# Power_supply.net
KiCad netlist of a schematic drawn in Altium Designer
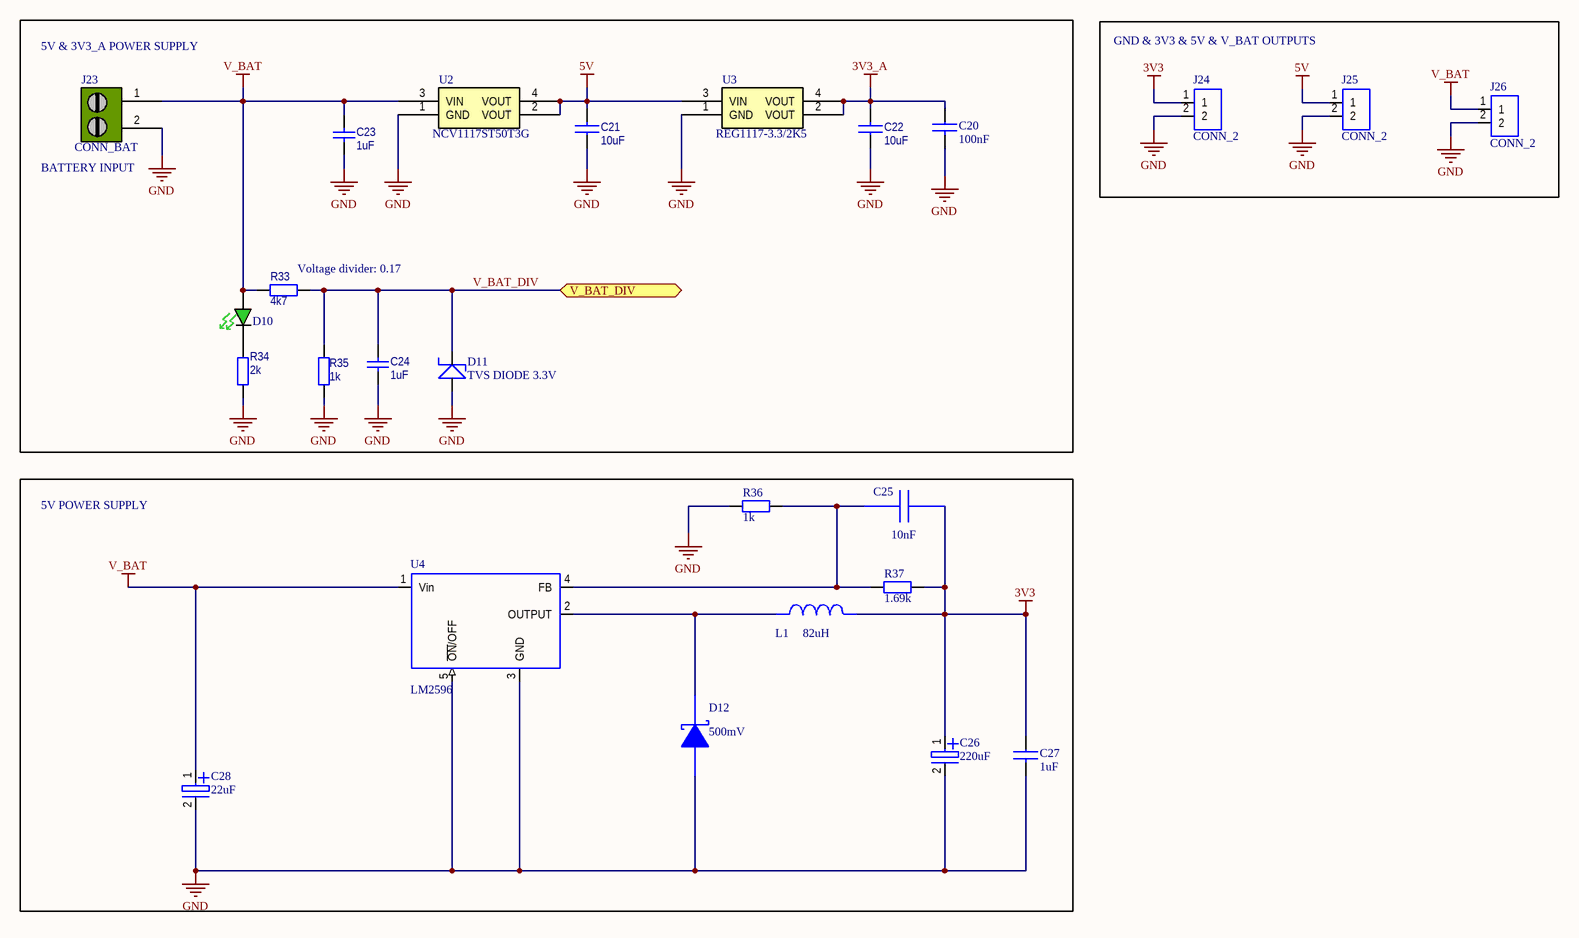
[diagram p0: Power_supply.SchDoc]

(export (version "E")
  (design (tool "Eeschema 10.0.6"))
  (components
    (comp (ref "C20")
      (value "100nF")
      (footprint "080503")
      (description "CAP CER 0.1UF 25V 10% X7R 0805")
      (libsource (lib "EISI") (part "CAPA"))
    )
    (comp (ref "C21")
      (value "10uF")
      (footprint "080501")
      (description "CAP CER 10UF 16V 20% X6S 0805")
      (libsource (lib "EISI") (part "CAPA"))
    )
    (comp (ref "C22")
      (value "10uF")
      (footprint "080501")
      (description "CAP CER 10UF 16V 20% X6S 0805")
      (libsource (lib "EISI") (part "CAPA"))
    )
    (comp (ref "C23")
      (value "1uF")
      (footprint "080503")
      (description "CAP CER 1UF 25V 10% X7R 0805")
      (libsource (lib "Miscellaneous Devices") (part "Cap Semi"))
    )
    (comp (ref "C24")
      (value "1uF")
      (footprint "080503")
      (description "CAP CER 1UF 25V 10% X7R 0805")
      (libsource (lib "Miscellaneous Devices") (part "Cap Semi"))
    )
    (comp (ref "C25")
      (value "10nF")
      (footprint "080503")
      (description "CAP CER 10nF 50V 10% X7R 0805")
      (libsource (lib "TI WEBENCH") (part "Cf"))
    )
    (comp (ref "C26")
      (value "220uF")
      (footprint "1411")
      (description "CAP TANT 220UF 4V 20% 1411")
      (libsource (lib "EISI") (part "CAPA_EL"))
    )
    (comp (ref "C27")
      (value "1uF")
      (footprint "080503")
      (description "CAP CER 1UF 25V 10% X7R 0805")
      (libsource (lib "EISI") (part "CAPA"))
    )
    (comp (ref "C28")
      (value "22uF")
      (footprint "2413")
      (description "CAP TANT 22UF 25V 10% 2413")
      (libsource (lib "EISI") (part "CAPA_EL"))
    )
    (comp (ref "D10")
      (value "LED")
      (footprint "LED_0805 - GREEN")
      (description "LED 2X1.2MM 570NM GN WTR CLR SMD")
      (libsource (lib "eDiode") (part "APT2012CGCK"))
    )
    (comp (ref "D11")
      (value "TVS DIODE 3.3V")
      (footprint "SOD-523")
      (description "TVS DIODE 3.3VWM 8VC SOD523")
      (libsource (lib "PalIncTest") (part "Zener"))
    )
    (comp (ref "D12")
      (value "500mV")
      (footprint "SMA")
      (description "B230A-13-F")
      (libsource (lib "TI WEBENCH") (part "D1"))
    )
    (comp (ref "J23")
      (value "CONN_BAT")
      (footprint "SL508_2C")
      (description "TERM BLOCK HDR 2POS R/A 5.08MM")
      (libsource (lib "eConnector") (part "282857-2"))
    )
    (comp (ref "J24")
      (value "CONN_2")
      (footprint "640454-2")
      (description "CONN HEADER 2.54mm 2")
      (libsource (lib "Aeroval") (part "CONN_2"))
    )
    (comp (ref "J25")
      (value "CONN_2")
      (footprint "640454-2")
      (description "CONN HEADER 2.54mm 2")
      (libsource (lib "Aeroval") (part "CONN_2"))
    )
    (comp (ref "J26")
      (value "CONN_2")
      (footprint "640454-2")
      (description "CONN HEADER 2.54mm 2")
      (libsource (lib "Aeroval") (part "CONN_2"))
    )
    (comp (ref "L1")
      (value "82uH")
      (footprint "L1")
      (description "SDR1307-820KL")
      (libsource (lib "TI WEBENCH") (part "L1"))
    )
    (comp (ref "R33")
      (value "4k7")
      (footprint "060301")
      (description "RES 4.7K 1% 0603")
      (libsource (lib "") (part "RES_3"))
    )
    (comp (ref "R34")
      (value "2k")
      (footprint "060301")
      (description "RES 2K 1% 0805")
      (libsource (lib "") (part "RES_1"))
    )
    (comp (ref "R35")
      (value "1k")
      (footprint "060301")
      (description "RES 1k 0805")
      (libsource (lib "") (part "RES_2"))
    )
    (comp (ref "R36")
      (value "1k")
      (footprint "060301")
      (description "RES 1k 0805")
      (libsource (lib "EISI") (part "RES"))
    )
    (comp (ref "R37")
      (value "1.69k")
      (footprint "060301")
      (description "RES 1.69K OHM 1% 1/8W 0805")
      (libsource (lib "EISI") (part "RES"))
    )
    (comp (ref "U2")
      (value "NCV1117ST50T3G")
      (footprint "SOT223")
      (description "Low Dropout (LDO) Regulators ANA 800mA LDO")
      (libsource (lib "eIC") (part "NCV1117ST50T3G"))
    )
    (comp (ref "U3")
      (value "REG1117-3.3/2K5")
      (footprint "SOT223")
      (description "IC REG LDO 3.3V 0.8A SOT223")
      (libsource (lib "eIC") (part "NCV1117ST50T3G"))
    )
    (comp (ref "U4")
      (value "LM2596")
      (footprint "TO263")
      (description "IC REG BUCK ADJ 3A TO263-5")
      (libsource (lib "Aeroval") (part "LM2596"))
    )
  )
  (nets
    (net (code "1") (name "/V_BAT_DIV") (class "Default")
      (node (ref "C24") (pin "1") (pinfunction "1_1") (pintype "passive"))
      (node (ref "D11") (pin "2") (pinfunction "2_2") (pintype "power_in"))
      (node (ref "R33") (pin "1") (pinfunction "1_1") (pintype "passive"))
      (node (ref "R35") (pin "1") (pinfunction "1_1") (pintype "passive"))
    )
    (net (code "2") (name "3V3") (class "Default")
      (node (ref "C25") (pin "1") (pinfunction "1_1") (pintype "passive"))
      (node (ref "C26") (pin "1") (pinfunction "1_1") (pintype "passive"))
      (node (ref "C27") (pin "1") (pinfunction "1_1") (pintype "passive"))
      (node (ref "J24") (pin "1") (pinfunction "1_1") (pintype "bidirectional"))
      (node (ref "L1") (pin "2") (pinfunction "2_2") (pintype "passive"))
      (node (ref "R37") (pin "2") (pinfunction "2_2") (pintype "passive"))
    )
    (net (code "3") (name "3V3_A") (class "Default")
      (node (ref "C20") (pin "1") (pinfunction "1_1") (pintype "passive"))
      (node (ref "C22") (pin "2") (pinfunction "2_2") (pintype "passive"))
      (node (ref "U3") (pin "2") (pinfunction "VOUT_2") (pintype "passive"))
      (node (ref "U3") (pin "4") (pinfunction "VOUT_4") (pintype "passive"))
    )
    (net (code "4") (name "5V") (class "Default")
      (node (ref "C21") (pin "2") (pinfunction "2_2") (pintype "passive"))
      (node (ref "J25") (pin "1") (pinfunction "1_1") (pintype "bidirectional"))
      (node (ref "U2") (pin "2") (pinfunction "VOUT_2") (pintype "passive"))
      (node (ref "U2") (pin "4") (pinfunction "VOUT_4") (pintype "passive"))
      (node (ref "U3") (pin "3") (pinfunction "VIN_3") (pintype "passive"))
    )
    (net (code "5") (name "GND") (class "Default")
      (node (ref "C20") (pin "2") (pinfunction "2_2") (pintype "passive"))
      (node (ref "C21") (pin "1") (pinfunction "1_1") (pintype "passive"))
      (node (ref "C22") (pin "1") (pinfunction "1_1") (pintype "passive"))
      (node (ref "C23") (pin "2") (pinfunction "2_2") (pintype "passive"))
      (node (ref "C24") (pin "2") (pinfunction "2_2") (pintype "passive"))
      (node (ref "C26") (pin "2") (pinfunction "2_2") (pintype "passive"))
      (node (ref "C27") (pin "2") (pinfunction "2_2") (pintype "passive"))
      (node (ref "C28") (pin "2") (pinfunction "2_2") (pintype "passive"))
      (node (ref "D11") (pin "1") (pinfunction "1_1") (pintype "power_in"))
      (node (ref "D12") (pin "2") (pinfunction "A_2") (pintype "passive"))
      (node (ref "J23") (pin "2") (pinfunction "2_2") (pintype "passive"))
      (node (ref "J24") (pin "2") (pinfunction "2_2") (pintype "bidirectional"))
      (node (ref "J25") (pin "2") (pinfunction "2_2") (pintype "bidirectional"))
      (node (ref "J26") (pin "2") (pinfunction "2_2") (pintype "bidirectional"))
      (node (ref "R34") (pin "1") (pinfunction "1_1") (pintype "passive"))
      (node (ref "R35") (pin "2") (pinfunction "2_2") (pintype "passive"))
      (node (ref "R36") (pin "1") (pinfunction "1_1") (pintype "passive"))
      (node (ref "U2") (pin "1") (pinfunction "GND_1") (pintype "passive"))
      (node (ref "U3") (pin "1") (pinfunction "GND_1") (pintype "passive"))
      (node (ref "U4") (pin "3") (pinfunction "GND_3") (pintype "power_in"))
      (node (ref "U4") (pin "5") (pinfunction "~{ON}/OFF_5") (pintype "input"))
    )
    (net (code "6") (name "Net-(D10-PadC)") (class "Default")
      (node (ref "D10") (pin "C") (pinfunction "C_C") (pintype "passive"))
      (node (ref "R34") (pin "2") (pinfunction "2_2") (pintype "passive"))
    )
    (net (code "7") (name "Net-(D12-K)") (class "Default")
      (node (ref "D12") (pin "1") (pinfunction "K_1") (pintype "passive"))
      (node (ref "L1") (pin "1") (pinfunction "1_1") (pintype "passive"))
      (node (ref "U4") (pin "2") (pinfunction "OUTPUT_2") (pintype "power_in"))
    )
    (net (code "8") (name "Net-(U4-FB)") (class "Default")
      (node (ref "C25") (pin "2") (pinfunction "2_2") (pintype "passive"))
      (node (ref "R36") (pin "2") (pinfunction "2_2") (pintype "passive"))
      (node (ref "R37") (pin "1") (pinfunction "1_1") (pintype "passive"))
      (node (ref "U4") (pin "4") (pinfunction "FB_4") (pintype "power_in"))
    )
    (net (code "9") (name "V_BAT") (class "Default")
      (node (ref "C23") (pin "1") (pinfunction "1_1") (pintype "passive"))
      (node (ref "C28") (pin "1") (pinfunction "1_1") (pintype "passive"))
      (node (ref "D10") (pin "A") (pinfunction "A_A") (pintype "passive"))
      (node (ref "J23") (pin "1") (pinfunction "1_1") (pintype "passive"))
      (node (ref "J26") (pin "1") (pinfunction "1_1") (pintype "bidirectional"))
      (node (ref "R33") (pin "2") (pinfunction "2_2") (pintype "passive"))
      (node (ref "U2") (pin "3") (pinfunction "VIN_3") (pintype "passive"))
      (node (ref "U4") (pin "1") (pinfunction "Vin_1") (pintype "power_in"))
    )
  )
)
